# Micro_RC_Receiver.net
KiCad netlist of a schematic drawn in EAGLE
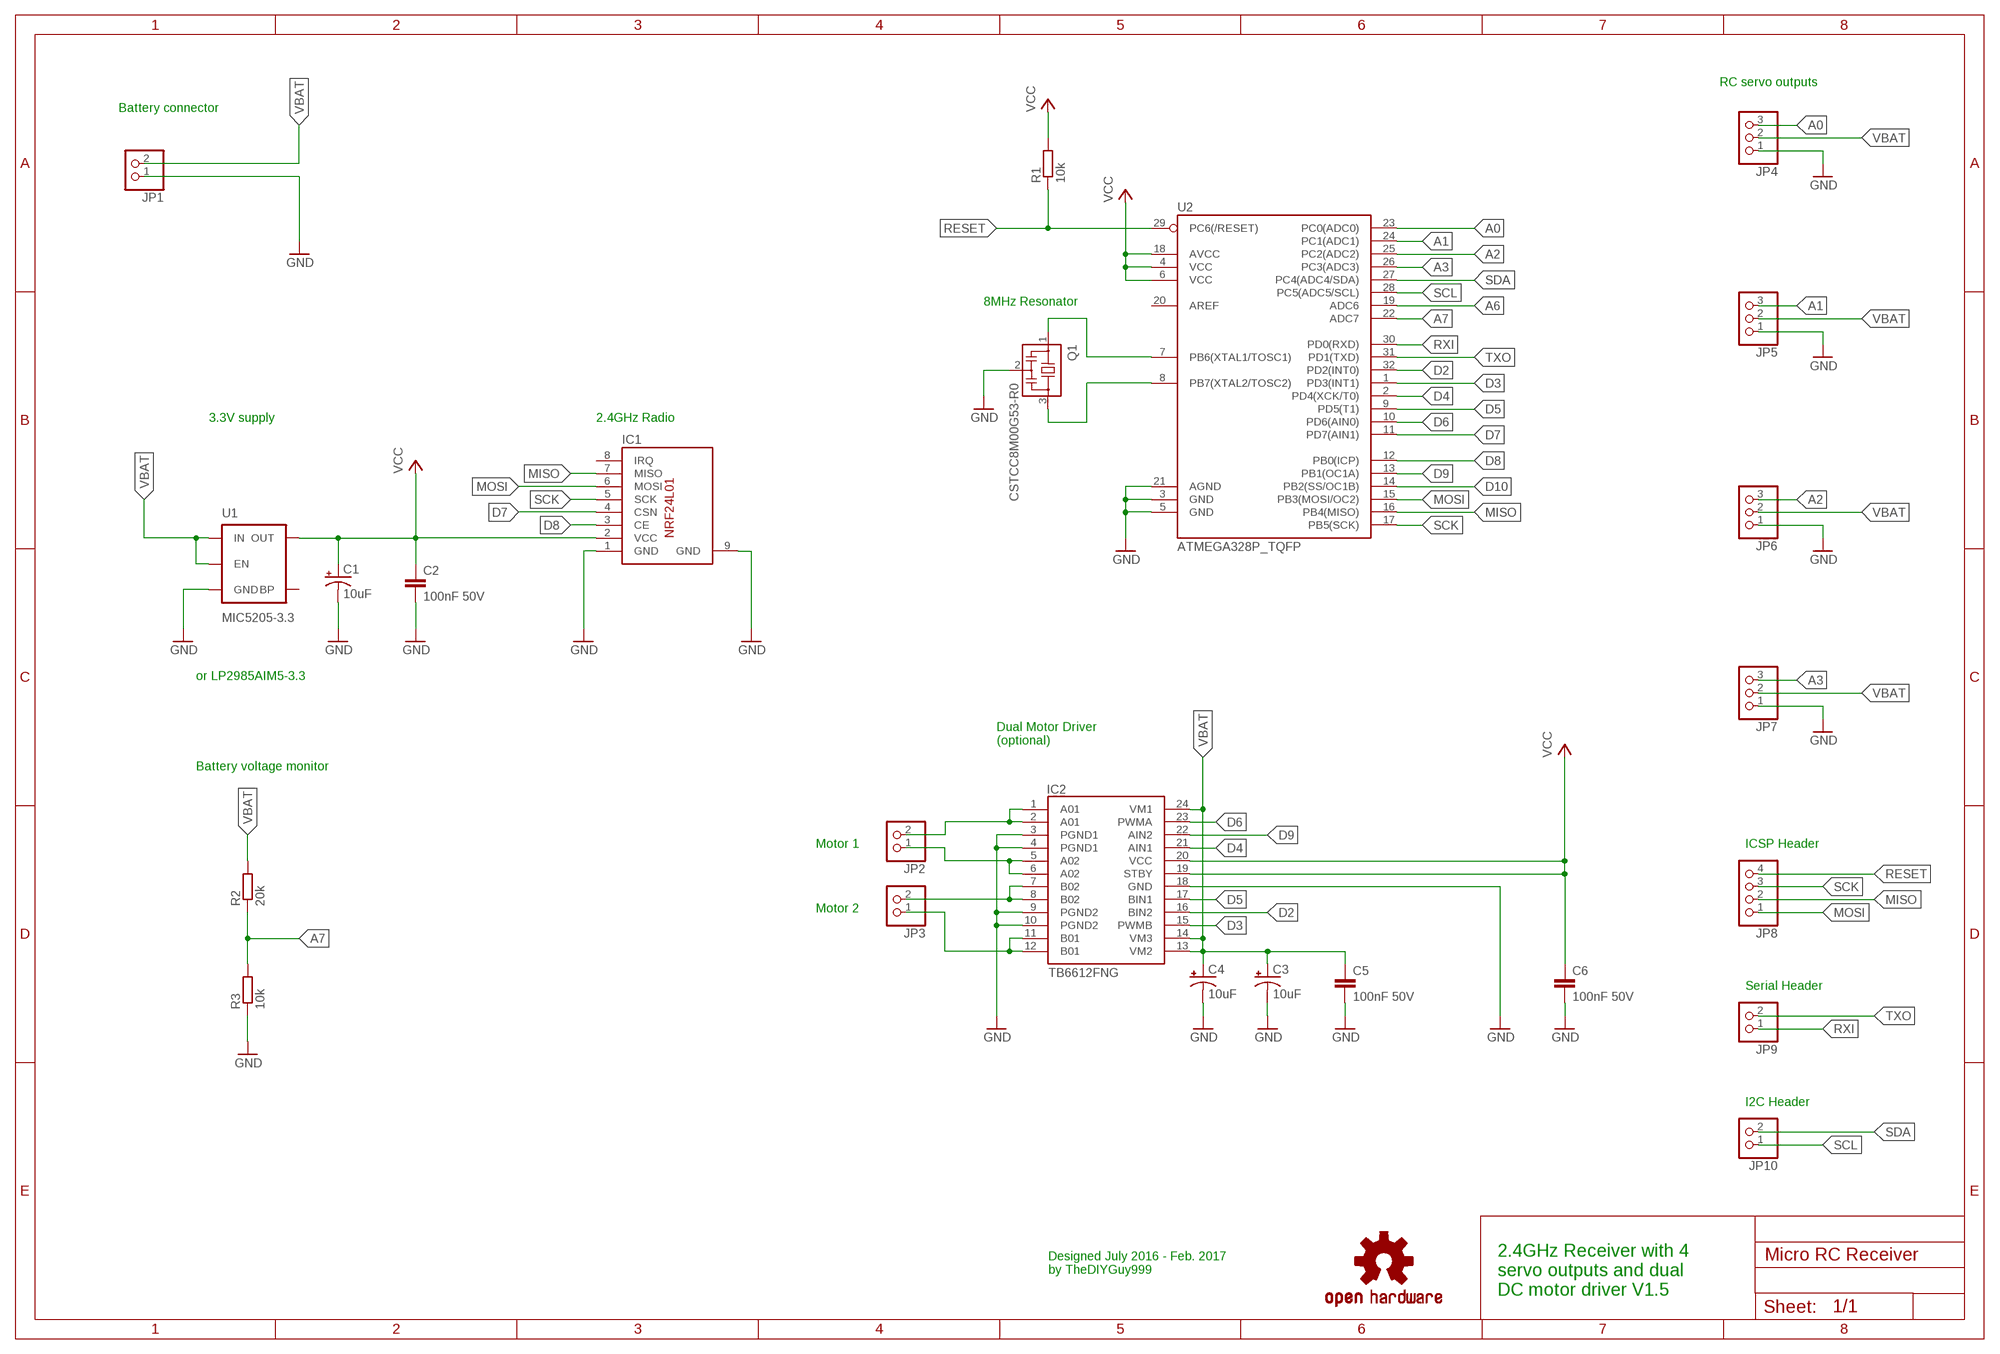
[diagram p0: schematic, sheet 1]

(export (version "E")
  (design (tool "Eeschema 10.0.6"))
  (components
    (comp (ref "C1")
      (value "10uF")
      (footprint "eagle-import:EIA3216")
      (libsource (lib "eagle-import") (part "10UF-16V-10%(TANT)"))
    )
    (comp (ref "C2")
      (value "100nF 50V")
      (footprint "eagle-import:C0805")
      (libsource (lib "eagle-import") (part "C-EUC0805"))
    )
    (comp (ref "C3")
      (value "10uF")
      (footprint "eagle-import:EIA3216")
      (libsource (lib "eagle-import") (part "10UF-16V-10%(TANT)"))
    )
    (comp (ref "C4")
      (value "10uF")
      (footprint "eagle-import:EIA3216")
      (libsource (lib "eagle-import") (part "10UF-16V-10%(TANT)"))
    )
    (comp (ref "C5")
      (value "100nF 50V")
      (footprint "eagle-import:C0805")
      (libsource (lib "eagle-import") (part "C-EUC0805"))
    )
    (comp (ref "C6")
      (value "100nF 50V")
      (footprint "eagle-import:C0805")
      (libsource (lib "eagle-import") (part "C-EUC0805"))
    )
    (comp (ref "IC1")
      (value "NRF24L01SMD")
      (footprint "eagle-import:NRF24L01_SMD")
      (libsource (lib "eagle-import") (part "NRF24L01SMD"))
    )
    (comp (ref "IC2")
      (value "TB6612FNG")
      (footprint "eagle-import:SSOP24")
      (libsource (lib "eagle-import") (part "TB6612FNG"))
    )
    (comp (ref "JP1")
      (value "PINHD-1X2")
      (footprint "eagle-import:1X02")
      (libsource (lib "eagle-import") (part "PINHD-1X2"))
    )
    (comp (ref "JP2")
      (value "PINHD-1X2")
      (footprint "eagle-import:1X02")
      (libsource (lib "eagle-import") (part "PINHD-1X2"))
    )
    (comp (ref "JP3")
      (value "PINHD-1X2")
      (footprint "eagle-import:1X02")
      (libsource (lib "eagle-import") (part "PINHD-1X2"))
    )
    (comp (ref "JP4")
      (value "PINHD-1X3")
      (footprint "eagle-import:1X03")
      (libsource (lib "eagle-import") (part "PINHD-1X3"))
    )
    (comp (ref "JP5")
      (value "PINHD-1X3")
      (footprint "eagle-import:1X03")
      (libsource (lib "eagle-import") (part "PINHD-1X3"))
    )
    (comp (ref "JP6")
      (value "PINHD-1X3")
      (footprint "eagle-import:1X03")
      (libsource (lib "eagle-import") (part "PINHD-1X3"))
    )
    (comp (ref "JP7")
      (value "PINHD-1X3")
      (footprint "eagle-import:1X03")
      (libsource (lib "eagle-import") (part "PINHD-1X3"))
    )
    (comp (ref "JP8")
      (value "PINHD-1X4")
      (footprint "eagle-import:1X04")
      (libsource (lib "eagle-import") (part "PINHD-1X4"))
    )
    (comp (ref "JP9")
      (value "PINHD-1X2")
      (footprint "eagle-import:1X02")
      (libsource (lib "eagle-import") (part "PINHD-1X2"))
    )
    (comp (ref "JP10")
      (value "PINHD-1X2")
      (footprint "eagle-import:1X02")
      (libsource (lib "eagle-import") (part "PINHD-1X2"))
    )
    (comp (ref "LOGO1")
      (value "OSHW-LOGOS")
      (footprint "eagle-import:OSHW-LOGO-S")
      (libsource (lib "eagle-import") (part "OSHW-LOGOS"))
    )
    (comp (ref "Q1")
      (value "CSTCC8M00G53-R0")
      (footprint "eagle-import:CSTCC")
      (libsource (lib "eagle-import") (part "CSTCC8M00G53-R0"))
    )
    (comp (ref "R1")
      (value "10k")
      (footprint "eagle-import:R0805")
      (libsource (lib "eagle-import") (part "R-EU_R0805"))
    )
    (comp (ref "R2")
      (value "20k")
      (footprint "eagle-import:R0805")
      (libsource (lib "eagle-import") (part "R-EU_R0805"))
    )
    (comp (ref "R3")
      (value "10k")
      (footprint "eagle-import:R0805")
      (libsource (lib "eagle-import") (part "R-EU_R0805"))
    )
    (comp (ref "U1")
      (value "MIC5205-3.3")
      (footprint "eagle-import:SOT23-5")
      (libsource (lib "eagle-import") (part "MIC52053.3V"))
    )
    (comp (ref "U2")
      (value "ATMEGA328P_TQFP")
      (footprint "eagle-import:TQFP32-08")
      (libsource (lib "eagle-import") (part "ATMEGA328P_TQFP"))
    )
  )
  (nets
    (net (code "1") (name "A0") (class "Default")
      (node (ref "JP4") (pin "3") (pinfunction "3_3") (pintype "passive"))
      (node (ref "U2") (pin "23") (pinfunction "PC0(ADC0)_23") (pintype "bidirectional"))
    )
    (net (code "2") (name "A1") (class "Default")
      (node (ref "JP5") (pin "3") (pinfunction "3_3") (pintype "passive"))
      (node (ref "U2") (pin "24") (pinfunction "PC1(ADC1)_24") (pintype "bidirectional"))
    )
    (net (code "3") (name "A2") (class "Default")
      (node (ref "JP6") (pin "3") (pinfunction "3_3") (pintype "passive"))
      (node (ref "U2") (pin "25") (pinfunction "PC2(ADC2)_25") (pintype "bidirectional"))
    )
    (net (code "4") (name "A3") (class "Default")
      (node (ref "JP7") (pin "3") (pinfunction "3_3") (pintype "passive"))
      (node (ref "U2") (pin "26") (pinfunction "PC3(ADC3)_26") (pintype "bidirectional"))
    )
    (net (code "5") (name "A6") (class "Default")
      (node (ref "U2") (pin "19") (pinfunction "ADC6_19") (pintype "bidirectional"))
    )
    (net (code "6") (name "A7") (class "Default")
      (node (ref "R2") (pin "1") (pinfunction "1_1") (pintype "passive"))
      (node (ref "R3") (pin "2") (pinfunction "2_2") (pintype "passive"))
      (node (ref "U2") (pin "22") (pinfunction "ADC7_22") (pintype "bidirectional"))
    )
    (net (code "7") (name "D2") (class "Default")
      (node (ref "IC2") (pin "16") (pinfunction "BIN2_16") (pintype "bidirectional"))
      (node (ref "U2") (pin "32") (pinfunction "PD2(INT0)_32") (pintype "bidirectional"))
    )
    (net (code "8") (name "D3") (class "Default")
      (node (ref "IC2") (pin "15") (pinfunction "PWMB_15") (pintype "bidirectional"))
      (node (ref "U2") (pin "1") (pinfunction "PD3(INT1)_1") (pintype "bidirectional"))
    )
    (net (code "9") (name "D4") (class "Default")
      (node (ref "IC2") (pin "21") (pinfunction "AIN1_21") (pintype "bidirectional"))
      (node (ref "U2") (pin "2") (pinfunction "PD4(XCK/T0)_2") (pintype "bidirectional"))
    )
    (net (code "10") (name "D5") (class "Default")
      (node (ref "IC2") (pin "17") (pinfunction "BIN1_17") (pintype "bidirectional"))
      (node (ref "U2") (pin "9") (pinfunction "PD5(T1)_9") (pintype "bidirectional"))
    )
    (net (code "11") (name "D6") (class "Default")
      (node (ref "IC2") (pin "23") (pinfunction "PWMA_23") (pintype "bidirectional"))
      (node (ref "U2") (pin "10") (pinfunction "PD6(AIN0)_10") (pintype "bidirectional"))
    )
    (net (code "12") (name "D7") (class "Default")
      (node (ref "IC1") (pin "4") (pinfunction "CSN_4") (pintype "bidirectional"))
      (node (ref "U2") (pin "11") (pinfunction "PD7(AIN1)_11") (pintype "bidirectional"))
    )
    (net (code "13") (name "D8") (class "Default")
      (node (ref "IC1") (pin "3") (pinfunction "CE_3") (pintype "bidirectional"))
      (node (ref "U2") (pin "12") (pinfunction "PB0(ICP)_12") (pintype "bidirectional"))
    )
    (net (code "14") (name "D9") (class "Default")
      (node (ref "IC2") (pin "22") (pinfunction "AIN2_22") (pintype "bidirectional"))
      (node (ref "U2") (pin "13") (pinfunction "PB1(OC1A)_13") (pintype "bidirectional"))
    )
    (net (code "15") (name "D10") (class "Default")
      (node (ref "U2") (pin "14") (pinfunction "PB2(SS/OC1B)_14") (pintype "bidirectional"))
    )
    (net (code "16") (name "GND") (class "Default")
      (node (ref "C1") (pin "C") (pinfunction "-_C") (pintype "passive"))
      (node (ref "C2") (pin "2") (pinfunction "2_2") (pintype "passive"))
      (node (ref "C3") (pin "C") (pinfunction "-_C") (pintype "passive"))
      (node (ref "C4") (pin "C") (pinfunction "-_C") (pintype "passive"))
      (node (ref "C5") (pin "2") (pinfunction "2_2") (pintype "passive"))
      (node (ref "C6") (pin "2") (pinfunction "2_2") (pintype "passive"))
      (node (ref "IC1") (pin "1") (pinfunction "GND_1") (pintype "bidirectional"))
      (node (ref "IC1") (pin "9") (pinfunction "GND_9") (pintype "bidirectional"))
      (node (ref "IC2") (pin "10") (pinfunction "PGND2_10") (pintype "bidirectional"))
      (node (ref "IC2") (pin "18") (pinfunction "GND_18") (pintype "bidirectional"))
      (node (ref "IC2") (pin "3") (pinfunction "PGND1_3") (pintype "bidirectional"))
      (node (ref "IC2") (pin "4") (pinfunction "PGND1_4") (pintype "bidirectional"))
      (node (ref "IC2") (pin "9") (pinfunction "PGND2_9") (pintype "bidirectional"))
      (node (ref "JP1") (pin "1") (pinfunction "1_1") (pintype "passive"))
      (node (ref "JP4") (pin "1") (pinfunction "1_1") (pintype "passive"))
      (node (ref "JP5") (pin "1") (pinfunction "1_1") (pintype "passive"))
      (node (ref "JP6") (pin "1") (pinfunction "1_1") (pintype "passive"))
      (node (ref "JP7") (pin "1") (pinfunction "1_1") (pintype "passive"))
      (node (ref "Q1") (pin "2") (pinfunction "2_2") (pintype "passive"))
      (node (ref "R3") (pin "1") (pinfunction "1_1") (pintype "passive"))
      (node (ref "U1") (pin "2") (pinfunction "GND_2") (pintype "input"))
      (node (ref "U2") (pin "21") (pinfunction "AGND_21") (pintype "bidirectional"))
      (node (ref "U2") (pin "3") (pinfunction "GND_3") (pintype "bidirectional"))
      (node (ref "U2") (pin "5") (pinfunction "GND_5") (pintype "bidirectional"))
    )
    (net (code "17") (name "MISO") (class "Default")
      (node (ref "IC1") (pin "7") (pinfunction "MISO_7") (pintype "bidirectional"))
      (node (ref "JP8") (pin "2") (pinfunction "2_2") (pintype "passive"))
      (node (ref "U2") (pin "16") (pinfunction "PB4(MISO)_16") (pintype "bidirectional"))
    )
    (net (code "18") (name "MOSI") (class "Default")
      (node (ref "IC1") (pin "6") (pinfunction "MOSI_6") (pintype "bidirectional"))
      (node (ref "JP8") (pin "1") (pinfunction "1_1") (pintype "passive"))
      (node (ref "U2") (pin "15") (pinfunction "PB3(MOSI/OC2)_15") (pintype "bidirectional"))
    )
    (net (code "19") (name "Net-(IC2-A01-Pad1)") (class "Default")
      (node (ref "IC2") (pin "1") (pinfunction "A01_1") (pintype "bidirectional"))
      (node (ref "IC2") (pin "2") (pinfunction "A01_2") (pintype "bidirectional"))
      (node (ref "JP2") (pin "2") (pinfunction "2_2") (pintype "passive"))
    )
    (net (code "20") (name "Net-(IC2-A02-Pad5)") (class "Default")
      (node (ref "IC2") (pin "5") (pinfunction "A02_5") (pintype "bidirectional"))
      (node (ref "IC2") (pin "6") (pinfunction "A02_6") (pintype "bidirectional"))
      (node (ref "JP2") (pin "1") (pinfunction "1_1") (pintype "passive"))
    )
    (net (code "21") (name "Net-(IC2-B01-Pad11)") (class "Default")
      (node (ref "IC2") (pin "11") (pinfunction "B01_11") (pintype "bidirectional"))
      (node (ref "IC2") (pin "12") (pinfunction "B01_12") (pintype "bidirectional"))
      (node (ref "JP3") (pin "1") (pinfunction "1_1") (pintype "passive"))
    )
    (net (code "22") (name "Net-(IC2-B02-Pad7)") (class "Default")
      (node (ref "IC2") (pin "7") (pinfunction "B02_7") (pintype "bidirectional"))
      (node (ref "IC2") (pin "8") (pinfunction "B02_8") (pintype "bidirectional"))
      (node (ref "JP3") (pin "2") (pinfunction "2_2") (pintype "passive"))
    )
    (net (code "23") (name "Net-(U2-PB6(XTAL1{slash}TOSC1))") (class "Default")
      (node (ref "Q1") (pin "1") (pinfunction "1_1") (pintype "passive"))
      (node (ref "U2") (pin "7") (pinfunction "PB6(XTAL1/TOSC1)_7") (pintype "bidirectional"))
    )
    (net (code "24") (name "Net-(U2-PB7(XTAL2{slash}TOSC2))") (class "Default")
      (node (ref "Q1") (pin "3") (pinfunction "3_3") (pintype "passive"))
      (node (ref "U2") (pin "8") (pinfunction "PB7(XTAL2/TOSC2)_8") (pintype "bidirectional"))
    )
    (net (code "25") (name "RESET") (class "Default")
      (node (ref "JP8") (pin "4") (pinfunction "4_4") (pintype "passive"))
      (node (ref "R1") (pin "1") (pinfunction "1_1") (pintype "passive"))
      (node (ref "U2") (pin "29") (pinfunction "PC6(/RESET)_29") (pintype "bidirectional"))
    )
    (net (code "26") (name "RXI") (class "Default")
      (node (ref "JP9") (pin "1") (pinfunction "1_1") (pintype "passive"))
      (node (ref "U2") (pin "30") (pinfunction "PD0(RXD)_30") (pintype "bidirectional"))
    )
    (net (code "27") (name "SCK") (class "Default")
      (node (ref "IC1") (pin "5") (pinfunction "SCK_5") (pintype "bidirectional"))
      (node (ref "JP8") (pin "3") (pinfunction "3_3") (pintype "passive"))
      (node (ref "U2") (pin "17") (pinfunction "PB5(SCK)_17") (pintype "bidirectional"))
    )
    (net (code "28") (name "SCL") (class "Default")
      (node (ref "JP10") (pin "1") (pinfunction "1_1") (pintype "passive"))
      (node (ref "U2") (pin "28") (pinfunction "PC5(ADC5/SCL)_28") (pintype "bidirectional"))
    )
    (net (code "29") (name "SDA") (class "Default")
      (node (ref "JP10") (pin "2") (pinfunction "2_2") (pintype "passive"))
      (node (ref "U2") (pin "27") (pinfunction "PC4(ADC4/SDA)_27") (pintype "bidirectional"))
    )
    (net (code "30") (name "TXO") (class "Default")
      (node (ref "JP9") (pin "2") (pinfunction "2_2") (pintype "passive"))
      (node (ref "U2") (pin "31") (pinfunction "PD1(TXD)_31") (pintype "bidirectional"))
    )
    (net (code "31") (name "VBAT") (class "Default")
      (node (ref "C3") (pin "A") (pinfunction "+_A") (pintype "passive"))
      (node (ref "C4") (pin "A") (pinfunction "+_A") (pintype "passive"))
      (node (ref "C5") (pin "1") (pinfunction "1_1") (pintype "passive"))
      (node (ref "IC2") (pin "13") (pinfunction "VM2_13") (pintype "bidirectional"))
      (node (ref "IC2") (pin "14") (pinfunction "VM3_14") (pintype "bidirectional"))
      (node (ref "IC2") (pin "24") (pinfunction "VM1_24") (pintype "bidirectional"))
      (node (ref "JP1") (pin "2") (pinfunction "2_2") (pintype "passive"))
      (node (ref "JP4") (pin "2") (pinfunction "2_2") (pintype "passive"))
      (node (ref "JP5") (pin "2") (pinfunction "2_2") (pintype "passive"))
      (node (ref "JP6") (pin "2") (pinfunction "2_2") (pintype "passive"))
      (node (ref "JP7") (pin "2") (pinfunction "2_2") (pintype "passive"))
      (node (ref "R2") (pin "2") (pinfunction "2_2") (pintype "passive"))
      (node (ref "U1") (pin "1") (pinfunction "IN_1") (pintype "input"))
      (node (ref "U1") (pin "3") (pinfunction "EN_3") (pintype "input"))
    )
    (net (code "32") (name "VCC") (class "Default")
      (node (ref "C1") (pin "A") (pinfunction "+_A") (pintype "passive"))
      (node (ref "C2") (pin "1") (pinfunction "1_1") (pintype "passive"))
      (node (ref "C6") (pin "1") (pinfunction "1_1") (pintype "passive"))
      (node (ref "IC1") (pin "2") (pinfunction "VCC_2") (pintype "bidirectional"))
      (node (ref "IC2") (pin "19") (pinfunction "STBY_19") (pintype "bidirectional"))
      (node (ref "IC2") (pin "20") (pinfunction "VCC_20") (pintype "bidirectional"))
      (node (ref "R1") (pin "2") (pinfunction "2_2") (pintype "passive"))
      (node (ref "U1") (pin "5") (pinfunction "OUT_5") (pintype "passive"))
      (node (ref "U2") (pin "18") (pinfunction "AVCC_18") (pintype "bidirectional"))
      (node (ref "U2") (pin "4") (pinfunction "VCC_4") (pintype "bidirectional"))
      (node (ref "U2") (pin "6") (pinfunction "VCC_6") (pintype "bidirectional"))
    )
    (net (code "33") (name "unconnected-(IC1-IRQ-Pad8)") (class "Default")
      (node (ref "IC1") (pin "8") (pinfunction "IRQ_8") (pintype "bidirectional"))
    )
    (net (code "34") (name "unconnected-(U1-BP-Pad4)") (class "Default")
      (node (ref "U1") (pin "4") (pinfunction "BP_4") (pintype "input"))
    )
    (net (code "35") (name "unconnected-(U2-AREF-Pad20)") (class "Default")
      (node (ref "U2") (pin "20") (pinfunction "AREF_20") (pintype "bidirectional"))
    )
  )
)
